# Sheet3.net
KiCad netlist of a schematic drawn in Altium Designer
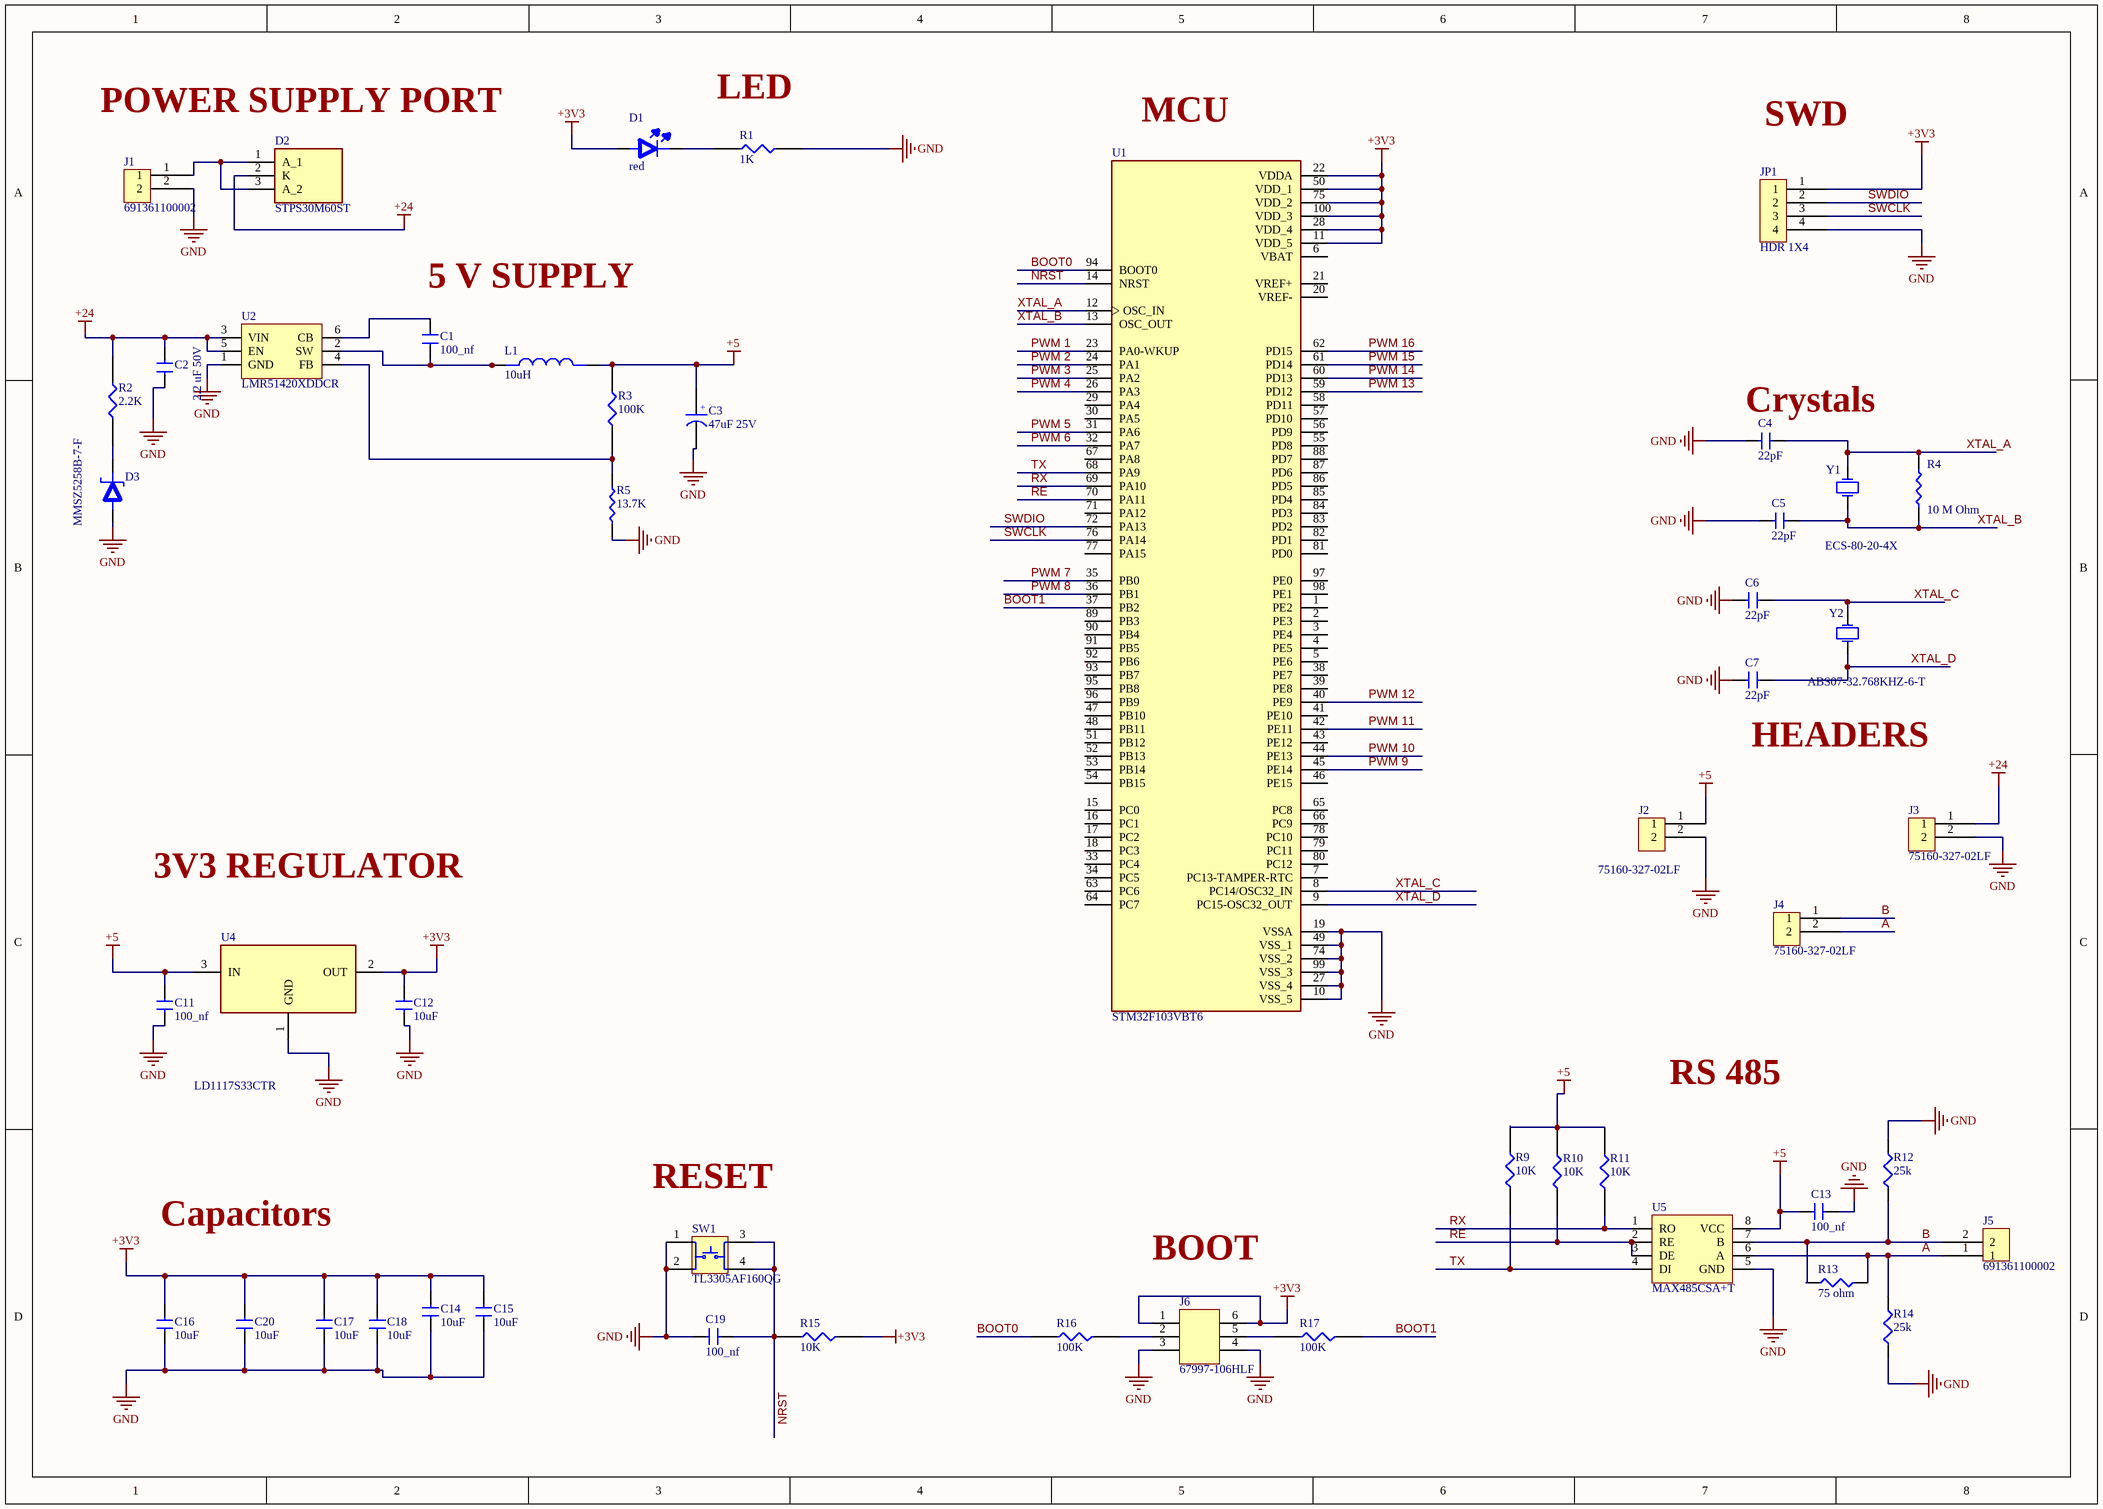
[diagram p0: Sheet3.SchDoc]

(export (version "E")
  (design (tool "Eeschema 10.0.6"))
  (components
    (comp (ref "C1")
      (value "100_nf")
      (footprint "CAP_0805")
      (description "Cap Ceramic 0.1uF 50V X7R 10% SMD 0805 125°C Blister Plastic T/R")
      (fields
        (field (name "MANUFACTURER") "TDK")
        (field (name "MANUFACTURER PART NUMBER") "C2012X7R1H104K125AE")
      )
      (libsource (lib "Component Schematic Library V1") (part "CAP_ 0.1uf"))
    )
    (comp (ref "C2")
      (value "2.2 uF 50V")
      (footprint "CAP_0805")
      (description "Cap Ceramic 2.2uF 50V JB 10% SMD 0805 85°C Blister Plastic T/R")
      (fields
        (field (name "MANUFACTURER") "TDK")
        (field (name "MANUFACTURER PART NUMBER") "C2012JB1H225K125AB")
      )
      (libsource (lib "Component Schematic Library V1") (part "cap 2.2 uf 50V 0808"))
    )
    (comp (ref "C3")
      (value "47uF 25V")
      (footprint "CAP_ALU_D_Size")
      (description "贴片铝电解电容 47uF ±20% 25V 1000hrs@85°C AEC_D6.3x5.4mm_SM")
      (fields
        (field (name "MANUFACTURER") "Panasonic")
        (field (name "MANUFACTURER PART NUMBER") "EEE-1EA470WP")
      )
      (libsource (lib "Component Schematic Library V1") (part "CAP_POLAR_47uF_25V"))
    )
    (comp (ref "C4")
      (value "22pF")
      (footprint "CAP_0805")
      (description "Cap Ceramic 22pF 50V C0G 0.25pF SMD 0805 125°C Paper T/R")
      (fields
        (field (name "MANUFACTURER") "KEMET")
        (field (name "MANUFACTURER PART NUMBER") "C0805C220C5GACTU")
      )
      (libsource (lib "STM Schematic Lib") (part "CAP_22pF"))
    )
    (comp (ref "C5")
      (value "22pF")
      (footprint "CAP_0805")
      (description "Cap Ceramic 22pF 50V C0G 0.25pF SMD 0805 125°C Paper T/R")
      (fields
        (field (name "MANUFACTURER") "KEMET")
        (field (name "MANUFACTURER PART NUMBER") "C0805C220C5GACTU")
      )
      (libsource (lib "STM Schematic Lib") (part "CAP_22pF"))
    )
    (comp (ref "C6")
      (value "22pF")
      (footprint "CAP_0805")
      (description "Cap Ceramic 22pF 50V C0G 0.25pF SMD 0805 125°C Paper T/R")
      (fields
        (field (name "MANUFACTURER") "KEMET")
        (field (name "MANUFACTURER PART NUMBER") "C0805C220C5GACTU")
      )
      (libsource (lib "STM Schematic Lib") (part "CAP_22pF"))
    )
    (comp (ref "C7")
      (value "22pF")
      (footprint "CAP_0805")
      (description "Cap Ceramic 22pF 50V C0G 0.25pF SMD 0805 125°C Paper T/R")
      (fields
        (field (name "MANUFACTURER") "KEMET")
        (field (name "MANUFACTURER PART NUMBER") "C0805C220C5GACTU")
      )
      (libsource (lib "STM Schematic Lib") (part "CAP_22pF"))
    )
    (comp (ref "C11")
      (value "100_nf")
      (footprint "CAP_0805")
      (description "Cap Ceramic 0.1uF 50V X7R 10% SMD 0805 125°C Blister Plastic T/R")
      (fields
        (field (name "MANUFACTURER") "TDK")
        (field (name "MANUFACTURER PART NUMBER") "C2012X7R1H104K125AE")
      )
      (libsource (lib "Component Schematic Library V1") (part "CAP_ 0.1uf"))
    )
    (comp (ref "C12")
      (value "10uF")
      (footprint "CAP_0805")
      (fields
        (field (name "MANUFACTURER") "TDK")
        (field (name "MANUFACTURER PART NUMBER") "C2012X5R1C106M125AC")
        (field (name "TOLERANCE") "20%")
      )
      (libsource (lib "Component Schematic Library V1") (part "CAP_10uF_0805"))
    )
    (comp (ref "C13")
      (value "100_nf")
      (footprint "CAP_0805")
      (description "Cap Ceramic 0.1uF 50V X7R 10% SMD 0805 125°C Blister Plastic T/R")
      (fields
        (field (name "MANUFACTURER") "TDK")
        (field (name "MANUFACTURER PART NUMBER") "C2012X7R1H104K125AE")
      )
      (libsource (lib "Component Schematic Library V1") (part "CAP_ 0.1uf"))
    )
    (comp (ref "C14")
      (value "10uF")
      (footprint "CAP_0805")
      (fields
        (field (name "MANUFACTURER") "TDK")
        (field (name "MANUFACTURER PART NUMBER") "C2012X5R1C106M125AC")
        (field (name "TOLERANCE") "20%")
      )
      (libsource (lib "Component Schematic Library V1") (part "CAP_10uF_0805"))
    )
    (comp (ref "C15")
      (value "10uF")
      (footprint "CAP_0805")
      (fields
        (field (name "MANUFACTURER") "TDK")
        (field (name "MANUFACTURER PART NUMBER") "C2012X5R1C106M125AC")
        (field (name "TOLERANCE") "20%")
      )
      (libsource (lib "Component Schematic Library V1") (part "CAP_10uF_0805"))
    )
    (comp (ref "C16")
      (value "10uF")
      (footprint "CAP_0805")
      (fields
        (field (name "MANUFACTURER") "TDK")
        (field (name "MANUFACTURER PART NUMBER") "C2012X5R1C106M125AC")
        (field (name "TOLERANCE") "20%")
      )
      (libsource (lib "Component Schematic Library V1") (part "CAP_10uF_0805"))
    )
    (comp (ref "C17")
      (value "10uF")
      (footprint "CAP_0805")
      (fields
        (field (name "MANUFACTURER") "TDK")
        (field (name "MANUFACTURER PART NUMBER") "C2012X5R1C106M125AC")
        (field (name "TOLERANCE") "20%")
      )
      (libsource (lib "Component Schematic Library V1") (part "CAP_10uF_0805"))
    )
    (comp (ref "C18")
      (value "10uF")
      (footprint "CAP_0805")
      (fields
        (field (name "MANUFACTURER") "TDK")
        (field (name "MANUFACTURER PART NUMBER") "C2012X5R1C106M125AC")
        (field (name "TOLERANCE") "20%")
      )
      (libsource (lib "Component Schematic Library V1") (part "CAP_10uF_0805"))
    )
    (comp (ref "C19")
      (value "100_nf")
      (footprint "CAP_0805")
      (description "Cap Ceramic 0.1uF 50V X7R 10% SMD 0805 125°C Blister Plastic T/R")
      (fields
        (field (name "MANUFACTURER") "TDK")
        (field (name "MANUFACTURER PART NUMBER") "C2012X7R1H104K125AE")
      )
      (libsource (lib "Component Schematic Library V1") (part "CAP_ 0.1uf"))
    )
    (comp (ref "C20")
      (value "10uF")
      (footprint "CAP_0805")
      (fields
        (field (name "MANUFACTURER") "TDK")
        (field (name "MANUFACTURER PART NUMBER") "C2012X5R1C106M125AC")
        (field (name "TOLERANCE") "20%")
      )
      (libsource (lib "Component Schematic Library V1") (part "CAP_10uF_0805"))
    )
    (comp (ref "D1")
      (value "red")
      (footprint "LED_RED_0805")
      (description "Led SMT Red 0805 Tape")
      (fields
        (field (name "MANUFACTURER") "Osram Opto")
        (field (name "MANUFACTURER PART NUMBER") "LSR976-NR-1")
      )
      (libsource (lib "STM Schematic Lib") (part "LED_RED"))
    )
    (comp (ref "D2")
      (value "STPS30M60ST")
      (footprint "TO255P460X1020X2008-3P")
      (description "Diode")
      (fields
        (field (name "MANUFACTURER") "STMicroelectronics")
        (field (name "MOUSER PART NUMBER") "511-STPS30M60ST")
      )
      (libsource (lib "Component Schematic Library V1") (part "STPS30M60ST"))
    )
    (comp (ref "D3")
      (value "MMSZ5258B-7-F")
      (footprint "SOD-123")
      (description "Diode Zener Single 36V 5% 500mW Automotive 2-Pin SOD-123 T/R")
      (fields (field (name "MANUFACTURER") "Diodes") (field (name "TOLERANCE") "5%"))
      (libsource (lib "Component Schematic Library V1") (part "Zener 36V"))
    )
    (comp (ref "J1")
      (value "691361100002")
      (footprint "Screw Terminal 3.5mm")
      (description "3611 Series 3.5mm Pitch Straight Pluggable Term Block; Plug; Cable Mount; 2 Way")
      (fields (field (name "MANUFACTURER") "Wurth Electronics") (field (name "VOLTAGE") "300V"))
      (libsource (lib "") (part "Screw Tarminal 3.5mm pitch_1"))
    )
    (comp (ref "J2")
      (value "75160-327-02LF")
      (footprint "HDR 1x2")
      (description "Conn Unshrouded Header HDR 2 POS 2.54mm Solder ST Thru-Hole Poly Bag")
      (fields (field (name "MANUFACTURER") "Amphenol ICC / FCI"))
      (libsource (lib "Component Schematic Library V1") (part "MALE_HDR_1X2"))
    )
    (comp (ref "J3")
      (value "75160-327-02LF")
      (footprint "HDR 1x2")
      (description "Conn Unshrouded Header HDR 2 POS 2.54mm Solder ST Thru-Hole Poly Bag")
      (fields (field (name "MANUFACTURER") "Amphenol ICC / FCI"))
      (libsource (lib "Component Schematic Library V1") (part "MALE_HDR_1X2"))
    )
    (comp (ref "J4")
      (value "75160-327-02LF")
      (footprint "HDR 1x2")
      (description "Conn Unshrouded Header HDR 2 POS 2.54mm Solder ST Thru-Hole Poly Bag")
      (fields (field (name "MANUFACTURER") "Amphenol ICC / FCI"))
      (libsource (lib "Component Schematic Library V1") (part "MALE_HDR_1X2"))
    )
    (comp (ref "J5")
      (value "691361100002")
      (footprint "Screw Terminal 3.5mm")
      (description "3611 Series 3.5mm Pitch Straight Pluggable Term Block; Plug; Cable Mount; 2 Way")
      (fields (field (name "MANUFACTURER") "Wurth Electronics") (field (name "VOLTAGE") "300V"))
      (libsource (lib "Component Schematic Library V1") (part "Screw Tarminal 3.5mm pitch"))
    )
    (comp (ref "J6")
      (value "67997-106HLF")
      (footprint "MALE_HDR_3X2_2.54mm")
      (description "Conn Unshrouded Header HDR 6 POS 2.54mm Solder ST Top Entry Thru-Hole BergStik® Bulk")
      (fields (field (name "MANUFACTURER") "Amphenol ICC / FCI"))
      (libsource (lib "Component Schematic Library V1") (part "Male_HDR_3X2_2.54mm_Pitch"))
    )
    (comp (ref "JP1")
      (value "HDR 1X4")
      (footprint "HDR 1X4")
      (description "Conn Unshrouded Header HDR 4 POS 2.54mm Solder ST Thru-Hole Bag")
      (fields
        (field (name "MANUFACTURER") "Amphenol ICC")
        (field (name "MANUFACTURER PART NUMBER") "68001-204HLF")
      )
      (libsource (lib "Component Schematic Library V1") (part "MALE_HDR_4X1_Unschrouded"))
    )
    (comp (ref "L1")
      (value "10uH")
      (footprint "B952AS-H-100M=P3")
      (description "Inductor Power Shielded Wirewound 10uH 20% 100KHz Ferrite 2.7A 0.044Ohm DCR 4040 T/R")
      (fields
        (field (name "MANUFACTURER") "Murata")
        (field (name "MANUFACTURER PART NUMBER") "#B952AS-H-100M=P3")
      )
      (libsource (lib "Component Schematic Library V1") (part "Inductor 10uH A"))
    )
    (comp (ref "R1")
      (value "1K")
      (footprint "R_0805")
      (description "贴片电阻 1000Ω ± 1.00% 0.125W ± 100ppm/℃ 0805")
      (fields
        (field (name "MANUFACTURER") "Yageo")
        (field (name "MANUFACTURER PART NUMBER") "RC0805FR-071KL")
      )
      (libsource (lib "Component Schematic Library V1") (part "RES_1_K_0805"))
    )
    (comp (ref "R2")
      (value "2.2K")
      (footprint "R_0805")
      (description "Res High Precision Thin Film 0805 2.2k Ohm 0.1% 1/8W ±15ppm/°C Molded Paper T/R")
      (fields
        (field (name "MANUFACTURER") "Yageo")
        (field (name "MANUFACTURER PART NUMBER") "RT0805BRC072K2L")
      )
      (libsource (lib "Component Schematic Library V1") (part "RES_2.2K 0805"))
    )
    (comp (ref "R3")
      (value "100K")
      (footprint "R_0805")
      (description "贴片电阻 100000Ω ± 1.00% 0.125W ± 100ppm/℃ 0805")
      (fields
        (field (name "MANUFACTURER") "Yageo")
        (field (name "MANUFACTURER PART NUMBER") "RC0805FR-07100KL")
      )
      (libsource (lib "Component Schematic Library V1") (part "RES_100_K_0805"))
    )
    (comp (ref "R4")
      (value "10 M Ohm")
      (footprint "R_0805")
      (description "贴片电阻 10000000Ω ± 1.00% 0.125W ± 100ppm/℃ 0805")
      (fields
        (field (name "MANUFACTURER") "Yageo")
        (field (name "MANUFACTURER PART NUMBER") "RC0805FR-0710ML")
      )
      (libsource (lib "STM Schematic Lib") (part "Res_10 M_Ohm"))
    )
    (comp (ref "R5")
      (value "13.7K")
      (footprint "R_0805")
      (description "Res Thick Film 0805 13.7K Ohm 1% 1/8W ±100ppm/°C SMD Paper T/R")
      (fields
        (field (name "MANUFACTURER") "Yageo")
        (field (name "MANUFACTURER PART NUMBER") "RC0805FR-0713K7L")
      )
      (libsource (lib "Component Schematic Library V1") (part "RES 13.7K 0805"))
    )
    (comp (ref "R9")
      (value "10K")
      (footprint "R_0805")
      (description "贴片电阻 10000Ω ± 1.00% 0.125W ± 100ppm/℃ 0805")
      (fields
        (field (name "MANUFACTURER") "Yageo")
        (field (name "MANUFACTURER PART NUMBER") "RC0805FR-0710KL")
      )
      (libsource (lib "Component Schematic Library V1") (part "RES_10_K_0805"))
    )
    (comp (ref "R10")
      (value "10K")
      (footprint "R_0805")
      (description "贴片电阻 10000Ω ± 1.00% 0.125W ± 100ppm/℃ 0805")
      (fields
        (field (name "MANUFACTURER") "Yageo")
        (field (name "MANUFACTURER PART NUMBER") "RC0805FR-0710KL")
      )
      (libsource (lib "Component Schematic Library V1") (part "RES_10_K_0805"))
    )
    (comp (ref "R11")
      (value "10K")
      (footprint "R_0805")
      (description "贴片电阻 10000Ω ± 1.00% 0.125W ± 100ppm/℃ 0805")
      (fields
        (field (name "MANUFACTURER") "Yageo")
        (field (name "MANUFACTURER PART NUMBER") "RC0805FR-0710KL")
      )
      (libsource (lib "Component Schematic Library V1") (part "RES_10_K_0805"))
    )
    (comp (ref "R12")
      (value "25k")
      (footprint "R_0805")
      (description "Res Thin Film 0805 25K Ohm 0.1% 1/10W ±25ppm/°C Molded SMD SMD Paper T/R")
      (fields
        (field (name "MANUFACTURER") "TE Connectivity")
        (field (name "MANUFACTURER PART NUMBER") "1614911-6")
      )
      (libsource (lib "Component Schematic Library V1") (part "RES 25K 0805"))
    )
    (comp (ref "R13")
      (value "75 ohm")
      (footprint "R_0805")
      (description "Anti-Sulfurated Chip Resistor Automotive Grade Thick Film 0805 75Ohm 5% Paper T/R")
      (fields
        (field (name "MANUFACTURER") "Yageo")
        (field (name "MANUFACTURER PART NUMBER") "AA0805JR-0775RL")
      )
      (libsource (lib "Component Schematic Library V1") (part "Res 75 ohm 0805"))
    )
    (comp (ref "R14")
      (value "25k")
      (footprint "R_0805")
      (description "Res Thin Film 0805 25K Ohm 0.1% 1/10W ±25ppm/°C Molded SMD SMD Paper T/R")
      (fields
        (field (name "MANUFACTURER") "TE Connectivity")
        (field (name "MANUFACTURER PART NUMBER") "1614911-6")
      )
      (libsource (lib "Component Schematic Library V1") (part "RES 25K 0805"))
    )
    (comp (ref "R15")
      (value "10K")
      (footprint "R_0805")
      (description "贴片电阻 10000Ω ± 1.00% 0.125W ± 100ppm/℃ 0805")
      (fields
        (field (name "MANUFACTURER") "Yageo")
        (field (name "MANUFACTURER PART NUMBER") "RC0805FR-0710KL")
      )
      (libsource (lib "Component Schematic Library V1") (part "RES_10_K_0805"))
    )
    (comp (ref "R16")
      (value "100K")
      (footprint "R_0805")
      (description "贴片电阻 100000Ω ± 1.00% 0.125W ± 100ppm/℃ 0805")
      (fields
        (field (name "MANUFACTURER") "Yageo")
        (field (name "MANUFACTURER PART NUMBER") "RC0805FR-07100KL")
      )
      (libsource (lib "Component Schematic Library V1") (part "RES_100_K_0805"))
    )
    (comp (ref "R17")
      (value "100K")
      (footprint "R_0805")
      (description "贴片电阻 100000Ω ± 1.00% 0.125W ± 100ppm/℃ 0805")
      (fields
        (field (name "MANUFACTURER") "Yageo")
        (field (name "MANUFACTURER PART NUMBER") "RC0805FR-07100KL")
      )
      (libsource (lib "Component Schematic Library V1") (part "RES_100_K_0805"))
    )
    (comp (ref "SW1")
      (value "TL3305AF160QG")
      (footprint "SW_PB_SMD")
      (description "TL3305A Series SPST 12 V 4.5 x 4.5 mm 160 gf Top Actuated SMT Tactile Switch")
      (fields (field (name "MANUFACTURER") "E-Switch"))
      (libsource (lib "STM Schematic Lib") (part "SW_PB"))
    )
    (comp (ref "U1")
      (value "STM32F103VBT6")
      (footprint "STM32F103VBT6")
      (description "ARM® Cortex®-M3 STM32 F1 Microcontroller IC 32-Bit 72MHz 128KB (128K x 8) FLASH")
      (fields (field (name "MANUFACTURER") "STMicroelectronics"))
      (libsource (lib "Component Schematic Library V1") (part "STM32F103VBT6"))
    )
    (comp (ref "U2")
      (value "LMR51420XDDCR")
      (footprint "SOT 23-6")
      (fields (field (name "MANUFACTURER") "Texas Instruments"))
      (libsource (lib "Component Schematic Library V1") (part "LMR51420XDDCR"))
    )
    (comp (ref "U4")
      (value "LD1117S33CTR")
      (footprint "SOT 223 3")
      (description "Linear Voltage Regulator IC Positive Fixed 1 Output 3.3V 800mA SOT-223")
      (fields (field (name "MANUFACTURER") "STMicroelectronics"))
      (libsource (lib "Component Schematic Library V1") (part "LDO 3V3"))
    )
    (comp (ref "U5")
      (value "MAX485CSA+T")
      (footprint "8 SOIC")
      (description "1/1 Transceiver Half RS422, RS485 8-SOIC")
      (fields (field (name "MANUFACTURER") "Maxim") (field (name "MANUFACTURER PART NUMBER") "MAX485CSA+"))
      (libsource (lib "Component Schematic Library V1") (part "MAX485CSA+"))
    )
    (comp (ref "Y1")
      (value "ECS-80-20-4X")
      (footprint "XTAL_8_MHZ")
      (description "Crystal 8MHz ±30ppm (Tol) ±50ppm (Stability) 20pF FUND 80Ohm 2-Pin HC-49/USX Thru-Hole Bulk")
      (fields (field (name "MANUFACTURER") "ECS International") (field (name "TOLERANCE") "30ppm"))
      (libsource (lib "STM Schematic Lib") (part "Xtal_8MHZ"))
    )
    (comp (ref "Y2")
      (value "ABS07-32.768KHZ-6-T")
      (footprint "XTAL_32.768 KHZ_SMD")
      (description "Crystal 0.032768MHz ±20ppm (Tol) 6pF Flexural 70000Ohm 2-Pin CSMD T/R")
      (fields (field (name "MANUFACTURER") "Abracon") (field (name "TOLERANCE") "20ppm"))
      (libsource (lib "STM Schematic Lib") (part "XTAl_32.768_KHZ"))
    )
  )
  (nets
    (net (code "1") (name "+3V3") (class "Default")
      (node (ref "C12") (pin "2") (pinfunction "2_2") (pintype "passive"))
      (node (ref "C14") (pin "1") (pinfunction "1_1") (pintype "passive"))
      (node (ref "C15") (pin "1") (pinfunction "1_1") (pintype "passive"))
      (node (ref "C16") (pin "1") (pinfunction "1_1") (pintype "passive"))
      (node (ref "C17") (pin "1") (pinfunction "1_1") (pintype "passive"))
      (node (ref "C18") (pin "1") (pinfunction "1_1") (pintype "passive"))
      (node (ref "C20") (pin "1") (pinfunction "1_1") (pintype "passive"))
      (node (ref "D1") (pin "2") (pinfunction "Anode_2") (pintype "passive"))
      (node (ref "J6") (pin "1") (pinfunction "1_1") (pintype "passive"))
      (node (ref "J6") (pin "6") (pinfunction "6_6") (pintype "passive"))
      (node (ref "JP1") (pin "1") (pinfunction "1_1") (pintype "passive"))
      (node (ref "R15") (pin "2") (pinfunction "3_2") (pintype "passive"))
      (node (ref "U1") (pin "100") (pinfunction "VDD_3_100") (pintype "passive"))
      (node (ref "U1") (pin "11") (pinfunction "VDD_5_11") (pintype "passive"))
      (node (ref "U1") (pin "22") (pinfunction "VDDA_22") (pintype "passive"))
      (node (ref "U1") (pin "28") (pinfunction "VDD_4_28") (pintype "passive"))
      (node (ref "U1") (pin "50") (pinfunction "VDD_1_50") (pintype "passive"))
      (node (ref "U1") (pin "75") (pinfunction "VDD_2_75") (pintype "passive"))
      (node (ref "U4") (pin "2") (pinfunction "OUT_2") (pintype "passive"))
    )
    (net (code "2") (name "+5") (class "Default")
      (node (ref "C11") (pin "1") (pinfunction "1_1") (pintype "passive"))
      (node (ref "C13") (pin "1") (pinfunction "1_1") (pintype "passive"))
      (node (ref "C3") (pin "1") (pinfunction "1_1") (pintype "passive"))
      (node (ref "J2") (pin "1") (pinfunction "1_1") (pintype "passive"))
      (node (ref "L1") (pin "2") (pinfunction "2_2") (pintype "passive"))
      (node (ref "R10") (pin "1") (pinfunction "2_1") (pintype "passive"))
      (node (ref "R11") (pin "1") (pinfunction "2_1") (pintype "passive"))
      (node (ref "R3") (pin "2") (pinfunction "3_2") (pintype "passive"))
      (node (ref "R9") (pin "1") (pinfunction "2_1") (pintype "passive"))
      (node (ref "U4") (pin "3") (pinfunction "IN_3") (pintype "passive"))
      (node (ref "U5") (pin "8") (pinfunction "VCC_8") (pintype "passive"))
    )
    (net (code "3") (name "+24") (class "Default")
      (node (ref "C2") (pin "1") (pinfunction "1_1") (pintype "passive"))
      (node (ref "D2") (pin "2") (pinfunction "K_2") (pintype "passive"))
      (node (ref "J3") (pin "1") (pinfunction "1_1") (pintype "passive"))
      (node (ref "R2") (pin "2") (pinfunction "3_2") (pintype "passive"))
      (node (ref "U2") (pin "3") (pinfunction "VIN_3") (pintype "passive"))
      (node (ref "U2") (pin "5") (pinfunction "EN_5") (pintype "passive"))
    )
    (net (code "4") (name "/A") (class "Default")
      (node (ref "J4") (pin "2") (pinfunction "2_2") (pintype "passive"))
      (node (ref "J5") (pin "1") (pinfunction "1_1") (pintype "passive"))
      (node (ref "R13") (pin "2") (pinfunction "3_2") (pintype "passive"))
      (node (ref "R14") (pin "2") (pinfunction "3_2") (pintype "passive"))
      (node (ref "U5") (pin "6") (pinfunction "A_6") (pintype "passive"))
    )
    (net (code "5") (name "/B") (class "Default")
      (node (ref "J4") (pin "1") (pinfunction "1_1") (pintype "passive"))
      (node (ref "J5") (pin "2") (pinfunction "2_2") (pintype "passive"))
      (node (ref "R12") (pin "1") (pinfunction "2_1") (pintype "passive"))
      (node (ref "R13") (pin "1") (pinfunction "2_1") (pintype "passive"))
      (node (ref "U5") (pin "7") (pinfunction "B_7") (pintype "passive"))
    )
    (net (code "6") (name "/BOOT0") (class "Default")
      (node (ref "R16") (pin "1") (pinfunction "2_1") (pintype "passive"))
      (node (ref "U1") (pin "94") (pinfunction "BOOT0_94") (pintype "passive"))
    )
    (net (code "7") (name "/BOOT1") (class "Default")
      (node (ref "R17") (pin "2") (pinfunction "3_2") (pintype "passive"))
      (node (ref "U1") (pin "37") (pinfunction "PB2_37") (pintype "passive"))
    )
    (net (code "8") (name "/NRST") (class "Default")
      (node (ref "C19") (pin "2") (pinfunction "2_2") (pintype "passive"))
      (node (ref "R15") (pin "1") (pinfunction "2_1") (pintype "passive"))
      (node (ref "SW1") (pin "3") (pinfunction "3_3") (pintype "passive"))
      (node (ref "SW1") (pin "4") (pinfunction "4_4") (pintype "passive"))
      (node (ref "U1") (pin "14") (pinfunction "NRST_14") (pintype "passive"))
    )
    (net (code "9") (name "/PWM 1") (class "Default")
      (node (ref "U1") (pin "23") (pinfunction "PA0-WKUP_23") (pintype "passive"))
    )
    (net (code "10") (name "/PWM 2") (class "Default")
      (node (ref "U1") (pin "24") (pinfunction "PA1_24") (pintype "passive"))
    )
    (net (code "11") (name "/PWM 3") (class "Default")
      (node (ref "U1") (pin "25") (pinfunction "PA2_25") (pintype "passive"))
    )
    (net (code "12") (name "/PWM 4") (class "Default")
      (node (ref "U1") (pin "26") (pinfunction "PA3_26") (pintype "passive"))
    )
    (net (code "13") (name "/PWM 5") (class "Default")
      (node (ref "U1") (pin "31") (pinfunction "PA6_31") (pintype "passive"))
    )
    (net (code "14") (name "/PWM 6") (class "Default")
      (node (ref "U1") (pin "32") (pinfunction "PA7_32") (pintype "passive"))
    )
    (net (code "15") (name "/PWM 7") (class "Default")
      (node (ref "U1") (pin "35") (pinfunction "PB0_35") (pintype "passive"))
    )
    (net (code "16") (name "/PWM 8") (class "Default")
      (node (ref "U1") (pin "36") (pinfunction "PB1_36") (pintype "passive"))
    )
    (net (code "17") (name "/PWM 9") (class "Default")
      (node (ref "U1") (pin "45") (pinfunction "PE14_45") (pintype "passive"))
    )
    (net (code "18") (name "/PWM 10") (class "Default")
      (node (ref "U1") (pin "44") (pinfunction "PE13_44") (pintype "passive"))
    )
    (net (code "19") (name "/PWM 11") (class "Default")
      (node (ref "U1") (pin "42") (pinfunction "PE11_42") (pintype "passive"))
    )
    (net (code "20") (name "/PWM 12") (class "Default")
      (node (ref "U1") (pin "40") (pinfunction "PE9_40") (pintype "passive"))
    )
    (net (code "21") (name "/PWM 13") (class "Default")
      (node (ref "U1") (pin "59") (pinfunction "PD12_59") (pintype "passive"))
    )
    (net (code "22") (name "/PWM 14") (class "Default")
      (node (ref "U1") (pin "60") (pinfunction "PD13_60") (pintype "passive"))
    )
    (net (code "23") (name "/PWM 15") (class "Default")
      (node (ref "U1") (pin "61") (pinfunction "PD14_61") (pintype "passive"))
    )
    (net (code "24") (name "/PWM 16") (class "Default")
      (node (ref "U1") (pin "62") (pinfunction "PD15_62") (pintype "passive"))
    )
    (net (code "25") (name "/RE") (class "Default")
      (node (ref "R10") (pin "2") (pinfunction "3_2") (pintype "passive"))
      (node (ref "U1") (pin "70") (pinfunction "PA11_70") (pintype "passive"))
      (node (ref "U5") (pin "2") (pinfunction "RE_2") (pintype "passive"))
      (node (ref "U5") (pin "3") (pinfunction "DE_3") (pintype "passive"))
    )
    (net (code "26") (name "/RX") (class "Default")
      (node (ref "R11") (pin "2") (pinfunction "3_2") (pintype "passive"))
      (node (ref "U1") (pin "69") (pinfunction "PA10_69") (pintype "passive"))
      (node (ref "U5") (pin "1") (pinfunction "RO_1") (pintype "passive"))
    )
    (net (code "27") (name "/SWCLK") (class "Default")
      (node (ref "JP1") (pin "3") (pinfunction "3_3") (pintype "passive"))
      (node (ref "U1") (pin "76") (pinfunction "PA14_76") (pintype "passive"))
    )
    (net (code "28") (name "/SWDIO") (class "Default")
      (node (ref "JP1") (pin "2") (pinfunction "2_2") (pintype "passive"))
      (node (ref "U1") (pin "72") (pinfunction "PA13_72") (pintype "passive"))
    )
    (net (code "29") (name "/TX") (class "Default")
      (node (ref "R9") (pin "2") (pinfunction "3_2") (pintype "passive"))
      (node (ref "U1") (pin "68") (pinfunction "PA9_68") (pintype "passive"))
      (node (ref "U5") (pin "4") (pinfunction "DI_4") (pintype "passive"))
    )
    (net (code "30") (name "/XTAL_A") (class "Default")
      (node (ref "C4") (pin "2") (pinfunction "2_2") (pintype "passive"))
      (node (ref "R4") (pin "1") (pinfunction "1_1") (pintype "passive"))
      (node (ref "U1") (pin "12") (pinfunction "OSC_IN_12") (pintype "passive"))
      (node (ref "Y1") (pin "1") (pinfunction "1_1") (pintype "passive"))
    )
    (net (code "31") (name "/XTAL_B") (class "Default")
      (node (ref "C5") (pin "2") (pinfunction "2_2") (pintype "passive"))
      (node (ref "R4") (pin "2") (pinfunction "2_2") (pintype "passive"))
      (node (ref "U1") (pin "13") (pinfunction "OSC_OUT_13") (pintype "passive"))
      (node (ref "Y1") (pin "2") (pinfunction "2_2") (pintype "passive"))
    )
    (net (code "32") (name "/XTAL_C") (class "Default")
      (node (ref "C6") (pin "2") (pinfunction "2_2") (pintype "passive"))
      (node (ref "U1") (pin "8") (pinfunction "PC14/OSC32_IN_8") (pintype "passive"))
      (node (ref "Y2") (pin "1") (pinfunction "1_1") (pintype "passive"))
    )
    (net (code "33") (name "/XTAL_D") (class "Default")
      (node (ref "C7") (pin "2") (pinfunction "2_2") (pintype "passive"))
      (node (ref "U1") (pin "9") (pinfunction "PC15-OSC32_OUT_9") (pintype "passive"))
      (node (ref "Y2") (pin "2") (pinfunction "2_2") (pintype "passive"))
    )
    (net (code "34") (name "GND") (class "Default")
      (node (ref "C11") (pin "2") (pinfunction "2_2") (pintype "passive"))
      (node (ref "C12") (pin "1") (pinfunction "1_1") (pintype "passive"))
      (node (ref "C13") (pin "2") (pinfunction "2_2") (pintype "passive"))
      (node (ref "C14") (pin "2") (pinfunction "2_2") (pintype "passive"))
      (node (ref "C15") (pin "2") (pinfunction "2_2") (pintype "passive"))
      (node (ref "C16") (pin "2") (pinfunction "2_2") (pintype "passive"))
      (node (ref "C17") (pin "2") (pinfunction "2_2") (pintype "passive"))
      (node (ref "C18") (pin "2") (pinfunction "2_2") (pintype "passive"))
      (node (ref "C19") (pin "1") (pinfunction "1_1") (pintype "passive"))
      (node (ref "C2") (pin "2") (pinfunction "2_2") (pintype "passive"))
      (node (ref "C20") (pin "2") (pinfunction "2_2") (pintype "passive"))
      (node (ref "C3") (pin "2") (pinfunction "2_2") (pintype "passive"))
      (node (ref "C4") (pin "1") (pinfunction "1_1") (pintype "passive"))
      (node (ref "C5") (pin "1") (pinfunction "1_1") (pintype "passive"))
      (node (ref "C6") (pin "1") (pinfunction "1_1") (pintype "passive"))
      (node (ref "C7") (pin "1") (pinfunction "1_1") (pintype "passive"))
      (node (ref "D3") (pin "2") (pinfunction "Anode_2") (pintype "passive"))
      (node (ref "J1") (pin "2") (pinfunction "2_2") (pintype "passive"))
      (node (ref "J2") (pin "2") (pinfunction "2_2") (pintype "passive"))
      (node (ref "J3") (pin "2") (pinfunction "2_2") (pintype "passive"))
      (node (ref "J6") (pin "3") (pinfunction "3_3") (pintype "passive"))
      (node (ref "J6") (pin "4") (pinfunction "4_4") (pintype "passive"))
      (node (ref "JP1") (pin "4") (pinfunction "4_4") (pintype "passive"))
      (node (ref "R1") (pin "2") (pinfunction "3_2") (pintype "passive"))
      (node (ref "R12") (pin "2") (pinfunction "3_2") (pintype "passive"))
      (node (ref "R14") (pin "1") (pinfunction "2_1") (pintype "passive"))
      (node (ref "R5") (pin "2") (pinfunction "2_2") (pintype "passive"))
      (node (ref "SW1") (pin "1") (pinfunction "1_1") (pintype "passive"))
      (node (ref "SW1") (pin "2") (pinfunction "2_2") (pintype "passive"))
      (node (ref "U1") (pin "10") (pinfunction "VSS_5_10") (pintype "passive"))
      (node (ref "U1") (pin "19") (pinfunction "VSSA_19") (pintype "passive"))
      (node (ref "U1") (pin "27") (pinfunction "VSS_4_27") (pintype "passive"))
      (node (ref "U1") (pin "49") (pinfunction "VSS_1_49") (pintype "passive"))
      (node (ref "U1") (pin "74") (pinfunction "VSS_2_74") (pintype "passive"))
      (node (ref "U1") (pin "99") (pinfunction "VSS_3_99") (pintype "passive"))
      (node (ref "U2") (pin "1") (pinfunction "GND_1") (pintype "passive"))
      (node (ref "U4") (pin "1") (pinfunction "GND_1") (pintype "passive"))
      (node (ref "U5") (pin "5") (pinfunction "GND_5") (pintype "passive"))
    )
    (net (code "35") (name "Net-(D1-Cathode)") (class "Default")
      (node (ref "D1") (pin "1") (pinfunction "Cathode_1") (pintype "passive"))
      (node (ref "R1") (pin "1") (pinfunction "2_1") (pintype "passive"))
    )
    (net (code "36") (name "Net-(D2-A_1)") (class "Default")
      (node (ref "D2") (pin "1") (pinfunction "A_1_1") (pintype "passive"))
      (node (ref "D2") (pin "3") (pinfunction "A_2_3") (pintype "passive"))
      (node (ref "J1") (pin "1") (pinfunction "1_1") (pintype "passive"))
    )
    (net (code "37") (name "Net-(D3-Cathode)") (class "Default")
      (node (ref "D3") (pin "1") (pinfunction "Cathode_1") (pintype "passive"))
      (node (ref "R2") (pin "1") (pinfunction "2_1") (pintype "passive"))
    )
    (net (code "38") (name "Net-(R3-2)") (class "Default")
      (node (ref "R3") (pin "1") (pinfunction "2_1") (pintype "passive"))
      (node (ref "R5") (pin "1") (pinfunction "1_1") (pintype "passive"))
      (node (ref "U2") (pin "4") (pinfunction "FB_4") (pintype "passive"))
    )
    (net (code "39") (name "Net-(R16-3)") (class "Default")
      (node (ref "J6") (pin "2") (pinfunction "2_2") (pintype "passive"))
      (node (ref "R16") (pin "2") (pinfunction "3_2") (pintype "passive"))
    )
    (net (code "40") (name "Net-(R17-2)") (class "Default")
      (node (ref "J6") (pin "5") (pinfunction "5_5") (pintype "passive"))
      (node (ref "R17") (pin "1") (pinfunction "2_1") (pintype "passive"))
    )
    (net (code "41") (name "Net-(U2-CB)") (class "Default")
      (node (ref "C1") (pin "1") (pinfunction "1_1") (pintype "passive"))
      (node (ref "U2") (pin "6") (pinfunction "CB_6") (pintype "passive"))
    )
    (net (code "42") (name "Net-(U2-SW)") (class "Default")
      (node (ref "C1") (pin "2") (pinfunction "2_2") (pintype "passive"))
      (node (ref "L1") (pin "1") (pinfunction "1_1") (pintype "passive"))
      (node (ref "U2") (pin "2") (pinfunction "SW_2") (pintype "passive"))
    )
    (net (code "43") (name "unconnected-(U1-PA4-Pad29)") (class "Default")
      (node (ref "U1") (pin "29") (pinfunction "PA4_29") (pintype "passive"))
    )
    (net (code "44") (name "unconnected-(U1-PA5-Pad30)") (class "Default")
      (node (ref "U1") (pin "30") (pinfunction "PA5_30") (pintype "passive"))
    )
    (net (code "45") (name "unconnected-(U1-PA8-Pad67)") (class "Default")
      (node (ref "U1") (pin "67") (pinfunction "PA8_67") (pintype "passive"))
    )
    (net (code "46") (name "unconnected-(U1-PA12-Pad71)") (class "Default")
      (node (ref "U1") (pin "71") (pinfunction "PA12_71") (pintype "passive"))
    )
    (net (code "47") (name "unconnected-(U1-PA15-Pad77)") (class "Default")
      (node (ref "U1") (pin "77") (pinfunction "PA15_77") (pintype "passive"))
    )
    (net (code "48") (name "unconnected-(U1-PB3-Pad89)") (class "Default")
      (node (ref "U1") (pin "89") (pinfunction "PB3_89") (pintype "passive"))
    )
    (net (code "49") (name "unconnected-(U1-PB4-Pad90)") (class "Default")
      (node (ref "U1") (pin "90") (pinfunction "PB4_90") (pintype "passive"))
    )
    (net (code "50") (name "unconnected-(U1-PB5-Pad91)") (class "Default")
      (node (ref "U1") (pin "91") (pinfunction "PB5_91") (pintype "passive"))
    )
    (net (code "51") (name "unconnected-(U1-PB6-Pad92)") (class "Default")
      (node (ref "U1") (pin "92") (pinfunction "PB6_92") (pintype "passive"))
    )
    (net (code "52") (name "unconnected-(U1-PB7-Pad93)") (class "Default")
      (node (ref "U1") (pin "93") (pinfunction "PB7_93") (pintype "passive"))
    )
    (net (code "53") (name "unconnected-(U1-PB8-Pad95)") (class "Default")
      (node (ref "U1") (pin "95") (pinfunction "PB8_95") (pintype "passive"))
    )
    (net (code "54") (name "unconnected-(U1-PB9-Pad96)") (class "Default")
      (node (ref "U1") (pin "96") (pinfunction "PB9_96") (pintype "passive"))
    )
    (net (code "55") (name "unconnected-(U1-PB10-Pad47)") (class "Default")
      (node (ref "U1") (pin "47") (pinfunction "PB10_47") (pintype "passive"))
    )
    (net (code "56") (name "unconnected-(U1-PB11-Pad48)") (class "Default")
      (node (ref "U1") (pin "48") (pinfunction "PB11_48") (pintype "passive"))
    )
    (net (code "57") (name "unconnected-(U1-PB12-Pad51)") (class "Default")
      (node (ref "U1") (pin "51") (pinfunction "PB12_51") (pintype "passive"))
    )
    (net (code "58") (name "unconnected-(U1-PB13-Pad52)") (class "Default")
      (node (ref "U1") (pin "52") (pinfunction "PB13_52") (pintype "passive"))
    )
    (net (code "59") (name "unconnected-(U1-PB14-Pad53)") (class "Default")
      (node (ref "U1") (pin "53") (pinfunction "PB14_53") (pintype "passive"))
    )
    (net (code "60") (name "unconnected-(U1-PB15-Pad54)") (class "Default")
      (node (ref "U1") (pin "54") (pinfunction "PB15_54") (pintype "passive"))
    )
    (net (code "61") (name "unconnected-(U1-PC0-Pad15)") (class "Default")
      (node (ref "U1") (pin "15") (pinfunction "PC0_15") (pintype "passive"))
    )
    (net (code "62") (name "unconnected-(U1-PC1-Pad16)") (class "Default")
      (node (ref "U1") (pin "16") (pinfunction "PC1_16") (pintype "passive"))
    )
    (net (code "63") (name "unconnected-(U1-PC2-Pad17)") (class "Default")
      (node (ref "U1") (pin "17") (pinfunction "PC2_17") (pintype "passive"))
    )
    (net (code "64") (name "unconnected-(U1-PC3-Pad18)") (class "Default")
      (node (ref "U1") (pin "18") (pinfunction "PC3_18") (pintype "passive"))
    )
    (net (code "65") (name "unconnected-(U1-PC4-Pad33)") (class "Default")
      (node (ref "U1") (pin "33") (pinfunction "PC4_33") (pintype "passive"))
    )
    (net (code "66") (name "unconnected-(U1-PC5-Pad34)") (class "Default")
      (node (ref "U1") (pin "34") (pinfunction "PC5_34") (pintype "passive"))
    )
    (net (code "67") (name "unconnected-(U1-PC6-Pad63)") (class "Default")
      (node (ref "U1") (pin "63") (pinfunction "PC6_63") (pintype "passive"))
    )
    (net (code "68") (name "unconnected-(U1-PC7-Pad64)") (class "Default")
      (node (ref "U1") (pin "64") (pinfunction "PC7_64") (pintype "passive"))
    )
    (net (code "69") (name "unconnected-(U1-PC8-Pad65)") (class "Default")
      (node (ref "U1") (pin "65") (pinfunction "PC8_65") (pintype "passive"))
    )
    (net (code "70") (name "unconnected-(U1-PC9-Pad66)") (class "Default")
      (node (ref "U1") (pin "66") (pinfunction "PC9_66") (pintype "passive"))
    )
    (net (code "71") (name "unconnected-(U1-PC10-Pad78)") (class "Default")
      (node (ref "U1") (pin "78") (pinfunction "PC10_78") (pintype "passive"))
    )
    (net (code "72") (name "unconnected-(U1-PC11-Pad79)") (class "Default")
      (node (ref "U1") (pin "79") (pinfunction "PC11_79") (pintype "passive"))
    )
    (net (code "73") (name "unconnected-(U1-PC12-Pad80)") (class "Default")
      (node (ref "U1") (pin "80") (pinfunction "PC12_80") (pintype "passive"))
    )
    (net (code "74") (name "unconnected-(U1-PC13-TAMPER-RTC-Pad7)") (class "Default")
      (node (ref "U1") (pin "7") (pinfunction "PC13-TAMPER-RTC_7") (pintype "passive"))
    )
    (net (code "75") (name "unconnected-(U1-PD0-Pad81)") (class "Default")
      (node (ref "U1") (pin "81") (pinfunction "PD0_81") (pintype "passive"))
    )
    (net (code "76") (name "unconnected-(U1-PD1-Pad82)") (class "Default")
      (node (ref "U1") (pin "82") (pinfunction "PD1_82") (pintype "passive"))
    )
    (net (code "77") (name "unconnected-(U1-PD2-Pad83)") (class "Default")
      (node (ref "U1") (pin "83") (pinfunction "PD2_83") (pintype "passive"))
    )
    (net (code "78") (name "unconnected-(U1-PD3-Pad84)") (class "Default")
      (node (ref "U1") (pin "84") (pinfunction "PD3_84") (pintype "passive"))
    )
    (net (code "79") (name "unconnected-(U1-PD4-Pad85)") (class "Default")
      (node (ref "U1") (pin "85") (pinfunction "PD4_85") (pintype "passive"))
    )
    (net (code "80") (name "unconnected-(U1-PD5-Pad86)") (class "Default")
      (node (ref "U1") (pin "86") (pinfunction "PD5_86") (pintype "passive"))
    )
    (net (code "81") (name "unconnected-(U1-PD6-Pad87)") (class "Default")
      (node (ref "U1") (pin "87") (pinfunction "PD6_87") (pintype "passive"))
    )
    (net (code "82") (name "unconnected-(U1-PD7-Pad88)") (class "Default")
      (node (ref "U1") (pin "88") (pinfunction "PD7_88") (pintype "passive"))
    )
    (net (code "83") (name "unconnected-(U1-PD8-Pad55)") (class "Default")
      (node (ref "U1") (pin "55") (pinfunction "PD8_55") (pintype "passive"))
    )
    (net (code "84") (name "unconnected-(U1-PD9-Pad56)") (class "Default")
      (node (ref "U1") (pin "56") (pinfunction "PD9_56") (pintype "passive"))
    )
    (net (code "85") (name "unconnected-(U1-PD10-Pad57)") (class "Default")
      (node (ref "U1") (pin "57") (pinfunction "PD10_57") (pintype "passive"))
    )
    (net (code "86") (name "unconnected-(U1-PD11-Pad58)") (class "Default")
      (node (ref "U1") (pin "58") (pinfunction "PD11_58") (pintype "passive"))
    )
    (net (code "87") (name "unconnected-(U1-PE0-Pad97)") (class "Default")
      (node (ref "U1") (pin "97") (pinfunction "PE0_97") (pintype "passive"))
    )
    (net (code "88") (name "unconnected-(U1-PE1-Pad98)") (class "Default")
      (node (ref "U1") (pin "98") (pinfunction "PE1_98") (pintype "passive"))
    )
    (net (code "89") (name "unconnected-(U1-PE2-Pad1)") (class "Default")
      (node (ref "U1") (pin "1") (pinfunction "PE2_1") (pintype "passive"))
    )
    (net (code "90") (name "unconnected-(U1-PE3-Pad2)") (class "Default")
      (node (ref "U1") (pin "2") (pinfunction "PE3_2") (pintype "passive"))
    )
    (net (code "91") (name "unconnected-(U1-PE4-Pad3)") (class "Default")
      (node (ref "U1") (pin "3") (pinfunction "PE4_3") (pintype "passive"))
    )
    (net (code "92") (name "unconnected-(U1-PE5-Pad4)") (class "Default")
      (node (ref "U1") (pin "4") (pinfunction "PE5_4") (pintype "passive"))
    )
    (net (code "93") (name "unconnected-(U1-PE6-Pad5)") (class "Default")
      (node (ref "U1") (pin "5") (pinfunction "PE6_5") (pintype "passive"))
    )
    (net (code "94") (name "unconnected-(U1-PE7-Pad38)") (class "Default")
      (node (ref "U1") (pin "38") (pinfunction "PE7_38") (pintype "passive"))
    )
    (net (code "95") (name "unconnected-(U1-PE8-Pad39)") (class "Default")
      (node (ref "U1") (pin "39") (pinfunction "PE8_39") (pintype "passive"))
    )
    (net (code "96") (name "unconnected-(U1-PE10-Pad41)") (class "Default")
      (node (ref "U1") (pin "41") (pinfunction "PE10_41") (pintype "passive"))
    )
    (net (code "97") (name "unconnected-(U1-PE12-Pad43)") (class "Default")
      (node (ref "U1") (pin "43") (pinfunction "PE12_43") (pintype "passive"))
    )
    (net (code "98") (name "unconnected-(U1-PE15-Pad46)") (class "Default")
      (node (ref "U1") (pin "46") (pinfunction "PE15_46") (pintype "passive"))
    )
    (net (code "99") (name "unconnected-(U1-VBAT-Pad6)") (class "Default")
      (node (ref "U1") (pin "6") (pinfunction "VBAT_6") (pintype "passive"))
    )
    (net (code "100") (name "unconnected-(U1-VREF+-Pad21)") (class "Default")
      (node (ref "U1") (pin "21") (pinfunction "VREF+_21") (pintype "passive"))
    )
    (net (code "101") (name "unconnected-(U1-VREF--Pad20)") (class "Default")
      (node (ref "U1") (pin "20") (pinfunction "VREF-_20") (pintype "passive"))
    )
  )
)
